# M896.net
KiCad netlist of a schematic drawn in EAGLE
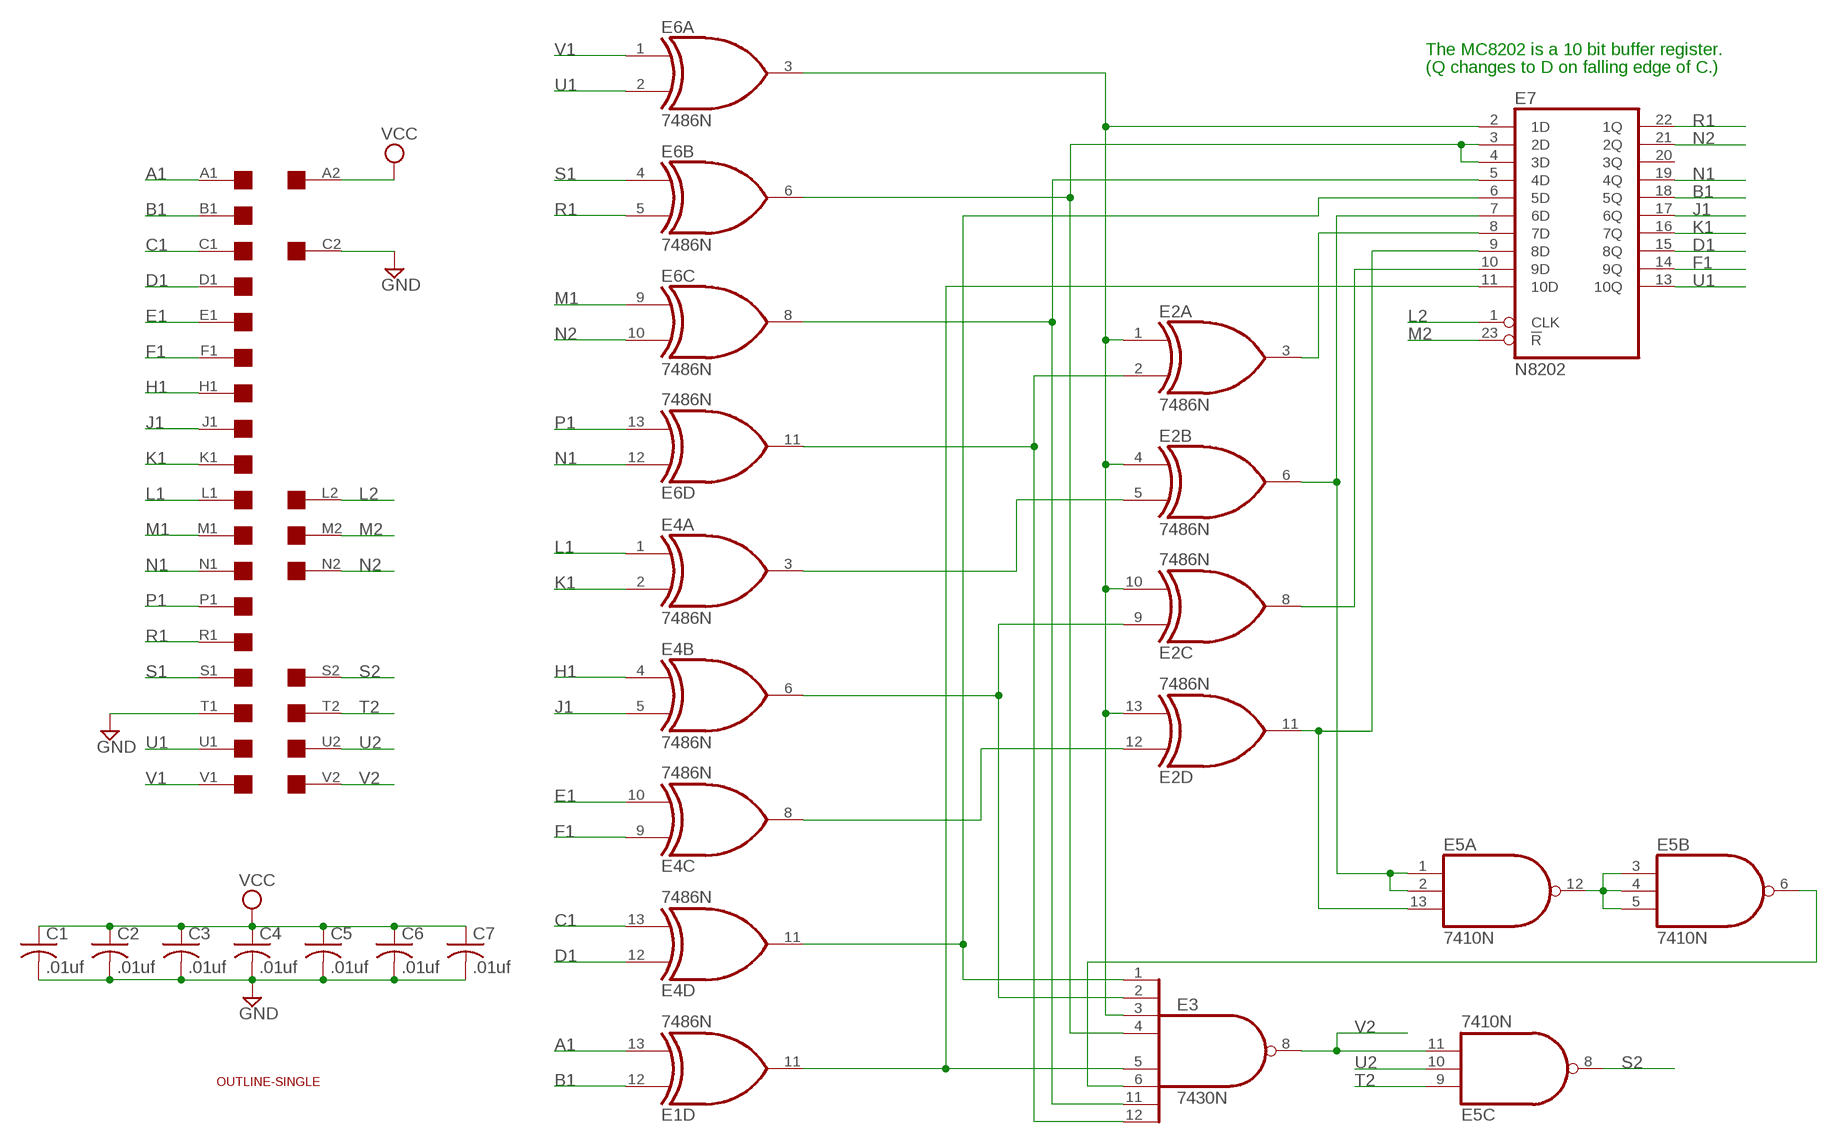
[diagram p0: schematic, sheet 1]

(export (version "E")
  (design (tool "Eeschema 10.0.6"))
  (components
    (comp (ref "C1")
      (value ".01uf")
      (footprint "eagle-import:C050-025X075")
      (libsource (lib "eagle-import") (part "C-US050-025X075"))
    )
    (comp (ref "C2")
      (value ".01uf")
      (footprint "eagle-import:C050-025X075")
      (libsource (lib "eagle-import") (part "C-US050-025X075"))
    )
    (comp (ref "C3")
      (value ".01uf")
      (footprint "eagle-import:C050-025X075")
      (libsource (lib "eagle-import") (part "C-US050-025X075"))
    )
    (comp (ref "C4")
      (value ".01uf")
      (footprint "eagle-import:C050-025X075")
      (libsource (lib "eagle-import") (part "C-US050-025X075"))
    )
    (comp (ref "C5")
      (value ".01uf")
      (footprint "eagle-import:C050-025X075")
      (libsource (lib "eagle-import") (part "C-US050-025X075"))
    )
    (comp (ref "C6")
      (value ".01uf")
      (footprint "eagle-import:C050-025X075")
      (libsource (lib "eagle-import") (part "C-US050-025X075"))
    )
    (comp (ref "C7")
      (value ".01uf")
      (footprint "eagle-import:C050-025X075")
      (libsource (lib "eagle-import") (part "C-US050-025X075"))
    )
    (comp (ref "E1")
      (value "7486N")
      (footprint "eagle-import:DIL14")
      (libsource (lib "eagle-import") (part "7486N"))
    )
    (comp (ref "E2")
      (value "7486N")
      (footprint "eagle-import:DIL14")
      (libsource (lib "eagle-import") (part "7486N"))
    )
    (comp (ref "E3")
      (value "7430N")
      (footprint "eagle-import:DIL14")
      (libsource (lib "eagle-import") (part "7430N"))
    )
    (comp (ref "E4")
      (value "7486N")
      (footprint "eagle-import:DIL14")
      (libsource (lib "eagle-import") (part "7486N"))
    )
    (comp (ref "E5")
      (value "7410N")
      (footprint "eagle-import:DIL14")
      (libsource (lib "eagle-import") (part "7410N"))
    )
    (comp (ref "E6")
      (value "7486N")
      (footprint "eagle-import:DIL14")
      (libsource (lib "eagle-import") (part "7486N"))
    )
    (comp (ref "E7")
      (value "N8202")
      (footprint "eagle-import:DIL24")
      (libsource (lib "eagle-import") (part "N8202"))
    )
    (comp (ref "U$1")
      (value "EDGE-2CONNECTOR")
      (footprint "eagle-import:EDGE-CON2")
      (libsource (lib "eagle-import") (part "EDGE-2CONNECTOR"))
    )
    (comp (ref "U$4")
      (value "OUTLINE-SINGLE")
      (footprint "eagle-import:SINGLE")
      (libsource (lib "eagle-import") (part "OUTLINE-SINGLE"))
    )
  )
  (nets
    (net (code "1") (name "/A1") (class "Default")
      (node (ref "E1") (pin "13") (pinfunction "I1_13") (pintype "input"))
      (node (ref "U$1") (pin "A1") (pinfunction "1_A1") (pintype "bidirectional"))
    )
    (net (code "2") (name "/B1") (class "Default")
      (node (ref "E1") (pin "12") (pinfunction "I0_12") (pintype "input"))
      (node (ref "E7") (pin "18") (pinfunction "5Q_18") (pintype "tri_state"))
      (node (ref "U$1") (pin "B1") (pinfunction "1_B1") (pintype "bidirectional"))
    )
    (net (code "3") (name "/C1") (class "Default")
      (node (ref "E4") (pin "13") (pinfunction "I1_13") (pintype "input"))
      (node (ref "U$1") (pin "C1") (pinfunction "1_C1") (pintype "bidirectional"))
    )
    (net (code "4") (name "/D1") (class "Default")
      (node (ref "E4") (pin "12") (pinfunction "I0_12") (pintype "input"))
      (node (ref "E7") (pin "15") (pinfunction "8Q_15") (pintype "tri_state"))
      (node (ref "U$1") (pin "D1") (pinfunction "1_D1") (pintype "bidirectional"))
    )
    (net (code "5") (name "/E1") (class "Default")
      (node (ref "E4") (pin "10") (pinfunction "I1_10") (pintype "input"))
      (node (ref "U$1") (pin "E1") (pinfunction "1_E1") (pintype "bidirectional"))
    )
    (net (code "6") (name "/F1") (class "Default")
      (node (ref "E4") (pin "9") (pinfunction "I0_9") (pintype "input"))
      (node (ref "E7") (pin "14") (pinfunction "9Q_14") (pintype "tri_state"))
      (node (ref "U$1") (pin "F1") (pinfunction "1_F1") (pintype "bidirectional"))
    )
    (net (code "7") (name "/H1") (class "Default")
      (node (ref "E4") (pin "4") (pinfunction "I0_4") (pintype "input"))
      (node (ref "U$1") (pin "H1") (pinfunction "1_H1") (pintype "bidirectional"))
    )
    (net (code "8") (name "/J1") (class "Default")
      (node (ref "E4") (pin "5") (pinfunction "I1_5") (pintype "input"))
      (node (ref "E7") (pin "17") (pinfunction "6Q_17") (pintype "tri_state"))
      (node (ref "U$1") (pin "J1") (pinfunction "1_J1") (pintype "bidirectional"))
    )
    (net (code "9") (name "/K1") (class "Default")
      (node (ref "E4") (pin "2") (pinfunction "I1_2") (pintype "input"))
      (node (ref "E7") (pin "16") (pinfunction "7Q_16") (pintype "tri_state"))
      (node (ref "U$1") (pin "K1") (pinfunction "1_K1") (pintype "bidirectional"))
    )
    (net (code "10") (name "/L1") (class "Default")
      (node (ref "E4") (pin "1") (pinfunction "I0_1") (pintype "input"))
      (node (ref "U$1") (pin "L1") (pinfunction "1_L1") (pintype "bidirectional"))
    )
    (net (code "11") (name "/L2") (class "Default")
      (node (ref "E7") (pin "1") (pinfunction "CLK_1") (pintype "input"))
      (node (ref "U$1") (pin "L2") (pinfunction "1_L2") (pintype "bidirectional"))
    )
    (net (code "12") (name "/M1") (class "Default")
      (node (ref "E6") (pin "9") (pinfunction "I0_9") (pintype "input"))
      (node (ref "U$1") (pin "M1") (pinfunction "1_M1") (pintype "bidirectional"))
    )
    (net (code "13") (name "/M2") (class "Default")
      (node (ref "E7") (pin "23") (pinfunction "~{R}_23") (pintype "input"))
      (node (ref "U$1") (pin "M2") (pinfunction "1_M2") (pintype "bidirectional"))
    )
    (net (code "14") (name "/N1") (class "Default")
      (node (ref "E6") (pin "12") (pinfunction "I0_12") (pintype "input"))
      (node (ref "E7") (pin "19") (pinfunction "4Q_19") (pintype "tri_state"))
      (node (ref "U$1") (pin "N1") (pinfunction "1_N1") (pintype "bidirectional"))
    )
    (net (code "15") (name "/N2") (class "Default")
      (node (ref "E6") (pin "10") (pinfunction "I1_10") (pintype "input"))
      (node (ref "E7") (pin "21") (pinfunction "2Q_21") (pintype "tri_state"))
      (node (ref "U$1") (pin "N2") (pinfunction "1_N2") (pintype "bidirectional"))
    )
    (net (code "16") (name "/P1") (class "Default")
      (node (ref "E6") (pin "13") (pinfunction "I1_13") (pintype "input"))
      (node (ref "U$1") (pin "P1") (pinfunction "1_P1") (pintype "bidirectional"))
    )
    (net (code "17") (name "/R1") (class "Default")
      (node (ref "E6") (pin "5") (pinfunction "I1_5") (pintype "input"))
      (node (ref "E7") (pin "22") (pinfunction "1Q_22") (pintype "tri_state"))
      (node (ref "U$1") (pin "R1") (pinfunction "1_R1") (pintype "bidirectional"))
    )
    (net (code "18") (name "/S1") (class "Default")
      (node (ref "E6") (pin "4") (pinfunction "I0_4") (pintype "input"))
      (node (ref "U$1") (pin "S1") (pinfunction "1_S1") (pintype "bidirectional"))
    )
    (net (code "19") (name "/S2") (class "Default")
      (node (ref "E5") (pin "8") (pinfunction "O_8") (pintype "output"))
      (node (ref "U$1") (pin "S2") (pinfunction "1_S2") (pintype "bidirectional"))
    )
    (net (code "20") (name "/T2") (class "Default")
      (node (ref "E5") (pin "9") (pinfunction "I0_9") (pintype "input"))
      (node (ref "U$1") (pin "T2") (pinfunction "1_T2") (pintype "bidirectional"))
    )
    (net (code "21") (name "/U1") (class "Default")
      (node (ref "E6") (pin "2") (pinfunction "I1_2") (pintype "input"))
      (node (ref "E7") (pin "13") (pinfunction "10Q_13") (pintype "tri_state"))
      (node (ref "U$1") (pin "U1") (pinfunction "1_U1") (pintype "bidirectional"))
    )
    (net (code "22") (name "/U2") (class "Default")
      (node (ref "E5") (pin "10") (pinfunction "I1_10") (pintype "input"))
      (node (ref "U$1") (pin "U2") (pinfunction "1_U2") (pintype "bidirectional"))
    )
    (net (code "23") (name "/V1") (class "Default")
      (node (ref "E6") (pin "1") (pinfunction "I0_1") (pintype "input"))
      (node (ref "U$1") (pin "V1") (pinfunction "1_V1") (pintype "bidirectional"))
    )
    (net (code "24") (name "/V2") (class "Default")
      (node (ref "E3") (pin "8") (pinfunction "O_8") (pintype "output"))
      (node (ref "E5") (pin "11") (pinfunction "I2_11") (pintype "input"))
      (node (ref "U$1") (pin "V2") (pinfunction "1_V2") (pintype "bidirectional"))
    )
    (net (code "25") (name "GND") (class "Default")
      (node (ref "C1") (pin "2") (pinfunction "2_2") (pintype "passive"))
      (node (ref "C2") (pin "2") (pinfunction "2_2") (pintype "passive"))
      (node (ref "C3") (pin "2") (pinfunction "2_2") (pintype "passive"))
      (node (ref "C4") (pin "2") (pinfunction "2_2") (pintype "passive"))
      (node (ref "C5") (pin "2") (pinfunction "2_2") (pintype "passive"))
      (node (ref "C6") (pin "2") (pinfunction "2_2") (pintype "passive"))
      (node (ref "C7") (pin "2") (pinfunction "2_2") (pintype "passive"))
      (node (ref "U$1") (pin "C2") (pinfunction "1_C2") (pintype "bidirectional"))
      (node (ref "U$1") (pin "T1") (pinfunction "1_T1") (pintype "bidirectional"))
    )
    (net (code "26") (name "Net-(E1D-O)") (class "Default")
      (node (ref "E1") (pin "11") (pinfunction "O_11") (pintype "output"))
      (node (ref "E3") (pin "5") (pinfunction "I4_5") (pintype "input"))
      (node (ref "E7") (pin "11") (pinfunction "10D_11") (pintype "input"))
    )
    (net (code "27") (name "Net-(E2A-I0)") (class "Default")
      (node (ref "E2") (pin "1") (pinfunction "I0_1") (pintype "input"))
      (node (ref "E2") (pin "10") (pinfunction "I1_10") (pintype "input"))
      (node (ref "E2") (pin "13") (pinfunction "I1_13") (pintype "input"))
      (node (ref "E2") (pin "4") (pinfunction "I0_4") (pintype "input"))
      (node (ref "E3") (pin "3") (pinfunction "I2_3") (pintype "input"))
      (node (ref "E6") (pin "3") (pinfunction "O_3") (pintype "output"))
      (node (ref "E7") (pin "2") (pinfunction "1D_2") (pintype "input"))
    )
    (net (code "28") (name "Net-(E2A-I1)") (class "Default")
      (node (ref "E2") (pin "2") (pinfunction "I1_2") (pintype "input"))
      (node (ref "E3") (pin "12") (pinfunction "I7_12") (pintype "input"))
      (node (ref "E6") (pin "11") (pinfunction "O_11") (pintype "output"))
    )
    (net (code "29") (name "Net-(E2A-O)") (class "Default")
      (node (ref "E2") (pin "3") (pinfunction "O_3") (pintype "output"))
      (node (ref "E7") (pin "8") (pinfunction "7D_8") (pintype "input"))
    )
    (net (code "30") (name "Net-(E2B-I1)") (class "Default")
      (node (ref "E2") (pin "5") (pinfunction "I1_5") (pintype "input"))
      (node (ref "E4") (pin "3") (pinfunction "O_3") (pintype "output"))
    )
    (net (code "31") (name "Net-(E2B-O)") (class "Default")
      (node (ref "E2") (pin "6") (pinfunction "O_6") (pintype "output"))
      (node (ref "E5") (pin "1") (pinfunction "I0_1") (pintype "input"))
      (node (ref "E5") (pin "2") (pinfunction "I1_2") (pintype "input"))
      (node (ref "E7") (pin "7") (pinfunction "6D_7") (pintype "input"))
    )
    (net (code "32") (name "Net-(E2C-I0)") (class "Default")
      (node (ref "E2") (pin "9") (pinfunction "I0_9") (pintype "input"))
      (node (ref "E3") (pin "2") (pinfunction "I1_2") (pintype "input"))
      (node (ref "E4") (pin "6") (pinfunction "O_6") (pintype "output"))
    )
    (net (code "33") (name "Net-(E2C-O)") (class "Default")
      (node (ref "E2") (pin "8") (pinfunction "O_8") (pintype "output"))
      (node (ref "E7") (pin "10") (pinfunction "9D_10") (pintype "input"))
    )
    (net (code "34") (name "Net-(E2D-I0)") (class "Default")
      (node (ref "E2") (pin "12") (pinfunction "I0_12") (pintype "input"))
      (node (ref "E4") (pin "8") (pinfunction "O_8") (pintype "output"))
    )
    (net (code "35") (name "Net-(E2D-O)") (class "Default")
      (node (ref "E2") (pin "11") (pinfunction "O_11") (pintype "output"))
      (node (ref "E5") (pin "13") (pinfunction "I2_13") (pintype "input"))
      (node (ref "E7") (pin "9") (pinfunction "8D_9") (pintype "input"))
    )
    (net (code "36") (name "Net-(E3A-I0)") (class "Default")
      (node (ref "E3") (pin "1") (pinfunction "I0_1") (pintype "input"))
      (node (ref "E4") (pin "11") (pinfunction "O_11") (pintype "output"))
      (node (ref "E7") (pin "6") (pinfunction "5D_6") (pintype "input"))
    )
    (net (code "37") (name "Net-(E3A-I3)") (class "Default")
      (node (ref "E3") (pin "4") (pinfunction "I3_4") (pintype "input"))
      (node (ref "E6") (pin "6") (pinfunction "O_6") (pintype "output"))
      (node (ref "E7") (pin "3") (pinfunction "2D_3") (pintype "input"))
      (node (ref "E7") (pin "4") (pinfunction "3D_4") (pintype "input"))
    )
    (net (code "38") (name "Net-(E3A-I5)") (class "Default")
      (node (ref "E3") (pin "6") (pinfunction "I5_6") (pintype "input"))
      (node (ref "E5") (pin "6") (pinfunction "O_6") (pintype "output"))
    )
    (net (code "39") (name "Net-(E3A-I6)") (class "Default")
      (node (ref "E3") (pin "11") (pinfunction "I6_11") (pintype "input"))
      (node (ref "E6") (pin "8") (pinfunction "O_8") (pintype "output"))
      (node (ref "E7") (pin "5") (pinfunction "4D_5") (pintype "input"))
    )
    (net (code "40") (name "Net-(E5A-O)") (class "Default")
      (node (ref "E5") (pin "12") (pinfunction "O_12") (pintype "output"))
      (node (ref "E5") (pin "3") (pinfunction "I0_3") (pintype "input"))
      (node (ref "E5") (pin "4") (pinfunction "I1_4") (pintype "input"))
      (node (ref "E5") (pin "5") (pinfunction "I2_5") (pintype "input"))
    )
    (net (code "41") (name "VCC") (class "Default")
      (node (ref "C1") (pin "1") (pinfunction "1_1") (pintype "passive"))
      (node (ref "C2") (pin "1") (pinfunction "1_1") (pintype "passive"))
      (node (ref "C3") (pin "1") (pinfunction "1_1") (pintype "passive"))
      (node (ref "C4") (pin "1") (pinfunction "1_1") (pintype "passive"))
      (node (ref "C5") (pin "1") (pinfunction "1_1") (pintype "passive"))
      (node (ref "C6") (pin "1") (pinfunction "1_1") (pintype "passive"))
      (node (ref "C7") (pin "1") (pinfunction "1_1") (pintype "passive"))
      (node (ref "U$1") (pin "A2") (pinfunction "1_A2") (pintype "bidirectional"))
    )
    (net (code "42") (name "unconnected-(E7A-3Q-Pad20)") (class "Default")
      (node (ref "E7") (pin "20") (pinfunction "3Q_20") (pintype "tri_state"))
    )
  )
)
